# Sheet1.net
KiCad netlist of a schematic drawn in Altium Designer
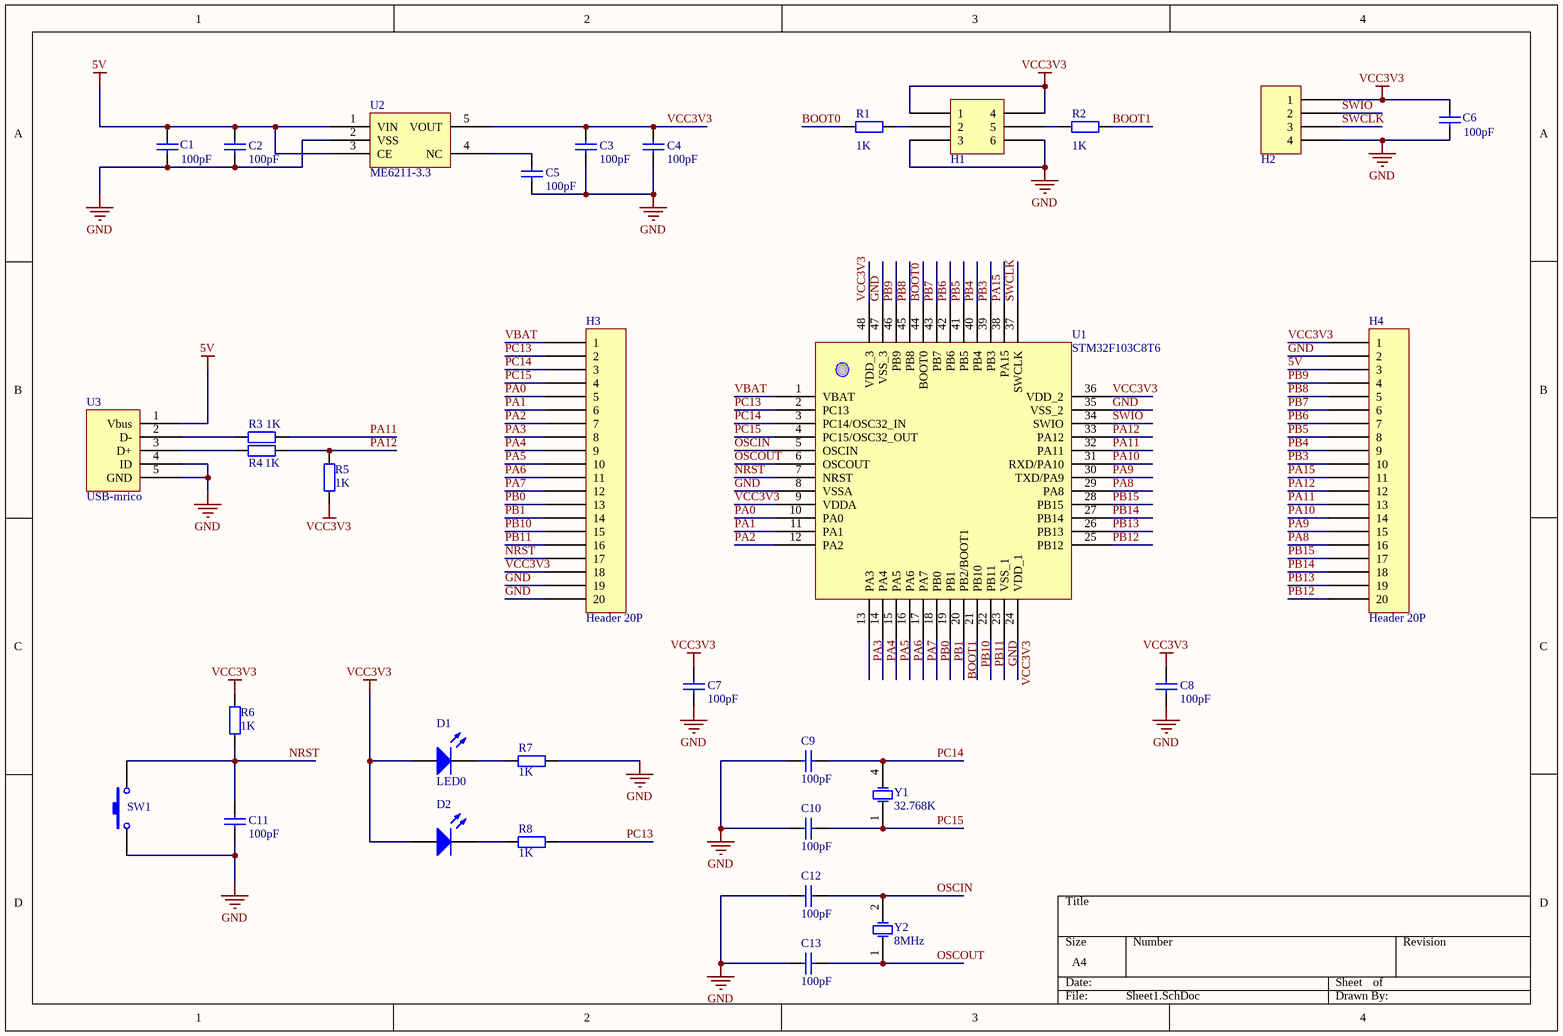
[diagram p0: Sheet1.SchDoc]

(export (version "E")
  (design (tool "Eeschema 10.0.6"))
  (components
    (comp (ref "C1")
      (value "100pF")
      (footprint "C 0603_L")
      (description "Capacitor")
      (fields (field (name "Comment") "Cap") (field (name "PUBLISHER") "Altium Limited"))
      (libsource (lib "Miscellaneous Devices") (part "Cap"))
    )
    (comp (ref "C2")
      (value "100pF")
      (footprint "C 0603_L")
      (description "Capacitor")
      (fields (field (name "Comment") "Cap") (field (name "PUBLISHER") "Altium Limited"))
      (libsource (lib "Miscellaneous Devices") (part "Cap"))
    )
    (comp (ref "C3")
      (value "100pF")
      (footprint "C 0603_L")
      (description "Capacitor")
      (fields (field (name "Comment") "Cap") (field (name "PUBLISHER") "Altium Limited"))
      (libsource (lib "Miscellaneous Devices") (part "Cap"))
    )
    (comp (ref "C4")
      (value "100pF")
      (footprint "C 0603_L")
      (description "Capacitor")
      (fields (field (name "Comment") "Cap") (field (name "PUBLISHER") "Altium Limited"))
      (libsource (lib "Miscellaneous Devices") (part "Cap"))
    )
    (comp (ref "C5")
      (value "100pF")
      (footprint "C 0805_L")
      (description "Capacitor")
      (fields (field (name "Comment") "Cap") (field (name "PUBLISHER") "Altium Limited"))
      (libsource (lib "Miscellaneous Devices") (part "Cap"))
    )
    (comp (ref "C6")
      (value "100pF")
      (footprint "C 0805_L")
      (description "Capacitor")
      (fields (field (name "Comment") "Cap") (field (name "PUBLISHER") "Altium Limited"))
      (libsource (lib "Miscellaneous Devices") (part "Cap"))
    )
    (comp (ref "C7")
      (value "100pF")
      (footprint "C 0603_L")
      (description "Capacitor")
      (fields (field (name "Comment") "Cap") (field (name "PUBLISHER") "Altium Limited"))
      (libsource (lib "Miscellaneous Devices") (part "Cap"))
    )
    (comp (ref "C8")
      (value "100pF")
      (footprint "C 0603_L")
      (description "Capacitor")
      (fields (field (name "Comment") "Cap") (field (name "PUBLISHER") "Altium Limited"))
      (libsource (lib "Miscellaneous Devices") (part "Cap"))
    )
    (comp (ref "C9")
      (value "100pF")
      (footprint "C 0603_L")
      (description "Capacitor")
      (fields (field (name "Comment") "Cap") (field (name "PUBLISHER") "Altium Limited"))
      (libsource (lib "Miscellaneous Devices") (part "Cap"))
    )
    (comp (ref "C10")
      (value "100pF")
      (footprint "C 0603_L")
      (description "Capacitor")
      (fields (field (name "Comment") "Cap") (field (name "PUBLISHER") "Altium Limited"))
      (libsource (lib "Miscellaneous Devices") (part "Cap"))
    )
    (comp (ref "C11")
      (value "100pF")
      (footprint "C 0603_L")
      (description "Capacitor")
      (fields (field (name "Comment") "Cap") (field (name "PUBLISHER") "Altium Limited"))
      (libsource (lib "Miscellaneous Devices") (part "Cap"))
    )
    (comp (ref "C12")
      (value "100pF")
      (footprint "C 0603_L")
      (description "Capacitor")
      (fields (field (name "Comment") "Cap") (field (name "PUBLISHER") "Altium Limited"))
      (libsource (lib "Miscellaneous Devices") (part "Cap"))
    )
    (comp (ref "C13")
      (value "100pF")
      (footprint "C 0603_L")
      (description "Capacitor")
      (fields (field (name "Comment") "Cap") (field (name "PUBLISHER") "Altium Limited"))
      (libsource (lib "Miscellaneous Devices") (part "Cap"))
    )
    (comp (ref "D1")
      (value "LED0")
      (footprint "LED 0603W")
      (description "Typical INFRARED GaAs LED")
      (fields (field (name "PUBLISHER") "Altium Limited"))
      (libsource (lib "Miscellaneous Devices") (part "LED0"))
    )
    (comp (ref "D2")
      (value "LED0")
      (footprint "LED 0603W")
      (description "Typical INFRARED GaAs LED")
      (fields (field (name "PUBLISHER") "Altium Limited"))
      (libsource (lib "Miscellaneous Devices") (part "LED0"))
    )
    (comp (ref "H1")
      (value "HEADER 6P")
      (footprint "HDR2.54-LI-2x3P")
      (libsource (lib "Schlib1") (part "HEADER 6P"))
    )
    (comp (ref "H2")
      (value "HEADER 4P")
      (footprint "HDR2.54-LI-4P")
      (libsource (lib "Schlib1") (part "HEADER 4P"))
    )
    (comp (ref "H3")
      (value "Header 20P")
      (footprint "HDR2.54-LI-20P")
      (libsource (lib "Schlib1") (part "HEADER 20P"))
    )
    (comp (ref "H4")
      (value "Header 20P")
      (footprint "HDR2.54-LI-20P")
      (libsource (lib "Schlib1") (part "HEADER 20P"))
    )
    (comp (ref "R1")
      (value "1K")
      (footprint "R 0603_L")
      (description "Resistor")
      (fields (field (name "Comment") "Res2") (field (name "PUBLISHER") "Altium Limited"))
      (libsource (lib "") (part "Res2_2"))
    )
    (comp (ref "R2")
      (value "1K")
      (footprint "R 0603_L")
      (description "Resistor")
      (fields (field (name "Comment") "Res2") (field (name "PUBLISHER") "Altium Limited"))
      (libsource (lib "") (part "Res2_2"))
    )
    (comp (ref "R3")
      (value "1K")
      (footprint "R 0603_L")
      (description "Resistor")
      (fields (field (name "Comment") "Res2") (field (name "PUBLISHER") "Altium Limited"))
      (libsource (lib "") (part "Res2_2"))
    )
    (comp (ref "R4")
      (value "1K")
      (footprint "R 0603_L")
      (description "Resistor")
      (fields (field (name "Comment") "Res2") (field (name "PUBLISHER") "Altium Limited"))
      (libsource (lib "") (part "Res2_2"))
    )
    (comp (ref "R5")
      (value "1K")
      (footprint "R 0603_L")
      (description "Resistor")
      (fields (field (name "Comment") "Res2") (field (name "PUBLISHER") "Altium Limited"))
      (libsource (lib "") (part "Res2_1"))
    )
    (comp (ref "R6")
      (value "1K")
      (footprint "R 0603_L")
      (description "Resistor")
      (fields (field (name "Comment") "Res2") (field (name "PUBLISHER") "Altium Limited"))
      (libsource (lib "") (part "Res2_1"))
    )
    (comp (ref "R7")
      (value "1K")
      (footprint "R 0603_L")
      (description "Resistor")
      (fields (field (name "Comment") "Res2") (field (name "PUBLISHER") "Altium Limited"))
      (libsource (lib "Miscellaneous Devices") (part "Res2"))
    )
    (comp (ref "R8")
      (value "1K")
      (footprint "R 0603_L")
      (description "Resistor")
      (fields (field (name "Comment") "Res2") (field (name "PUBLISHER") "Altium Limited"))
      (libsource (lib "Miscellaneous Devices") (part "Res2"))
    )
    (comp (ref "SW1")
      (value "SW-PB")
      (footprint "TSW SMD-3*6*4.3")
      (description "Switch")
      (fields (field (name "PUBLISHER") "Altium Limited"))
      (libsource (lib "Miscellaneous Devices") (part "SW-PB"))
    )
    (comp (ref "U1")
      (value "STM32F103C8T6")
      (footprint "LQFP48_N")
      (libsource (lib "Schlib1") (part "STM32F103C8T6"))
    )
    (comp (ref "U2")
      (value "ME6211-3.3")
      (footprint "SOT23-5")
      (libsource (lib "Schlib1") (part "ME6211-3.3"))
    )
    (comp (ref "U3")
      (value "USB-mrico")
      (footprint "USB-MICRO_B")
      (libsource (lib "Schlib1") (part "USB-mrico"))
    )
    (comp (ref "Y1")
      (value "32.768K")
      (footprint "OSC MC-306")
      (description "Crystal Oscillator")
      (fields (field (name "PUBLISHER") "Altium Limited"))
      (libsource (lib "Miscellaneous Devices") (part "XTAL"))
    )
    (comp (ref "Y2")
      (value "8MHz")
      (footprint "OSC HC-49S")
      (description "Crystal Oscillator")
      (fields (field (name "PUBLISHER") "Altium Limited"))
      (libsource (lib "") (part "XTAL_1"))
    )
  )
  (nets
    (net (code "1") (name "/BOOT0") (class "Default")
      (node (ref "R1") (pin "1") (pinfunction "1_1") (pintype "passive"))
      (node (ref "U1") (pin "44") (pinfunction "BOOT0_44") (pintype "passive"))
    )
    (net (code "2") (name "/BOOT1") (class "Default")
      (node (ref "R2") (pin "2") (pinfunction "2_2") (pintype "passive"))
      (node (ref "U1") (pin "20") (pinfunction "PB2/BOOT1_20") (pintype "passive"))
    )
    (net (code "3") (name "/NRST") (class "Default")
      (node (ref "C11") (pin "2") (pinfunction "2_2") (pintype "passive"))
      (node (ref "H3") (pin "17") (pinfunction "17_17") (pintype "passive"))
      (node (ref "R6") (pin "1") (pinfunction "1_1") (pintype "passive"))
      (node (ref "SW1") (pin "2") (pinfunction "2_2") (pintype "passive"))
      (node (ref "U1") (pin "7") (pinfunction "NRST_7") (pintype "passive"))
    )
    (net (code "4") (name "/OSCIN") (class "Default")
      (node (ref "C12") (pin "1") (pinfunction "1_1") (pintype "passive"))
      (node (ref "U1") (pin "5") (pinfunction "OSCIN_5") (pintype "passive"))
      (node (ref "Y2") (pin "2") (pinfunction "OSC2_2") (pintype "passive"))
    )
    (net (code "5") (name "/OSCOUT") (class "Default")
      (node (ref "C13") (pin "1") (pinfunction "1_1") (pintype "passive"))
      (node (ref "U1") (pin "6") (pinfunction "OSCOUT_6") (pintype "passive"))
      (node (ref "Y2") (pin "1") (pinfunction "OSC1_1") (pintype "passive"))
    )
    (net (code "6") (name "/PA0") (class "Default")
      (node (ref "H3") (pin "5") (pinfunction "5_5") (pintype "passive"))
      (node (ref "U1") (pin "10") (pinfunction "PA0_10") (pintype "passive"))
    )
    (net (code "7") (name "/PA1") (class "Default")
      (node (ref "H3") (pin "6") (pinfunction "6_6") (pintype "passive"))
      (node (ref "U1") (pin "11") (pinfunction "PA1_11") (pintype "passive"))
    )
    (net (code "8") (name "/PA2") (class "Default")
      (node (ref "H3") (pin "7") (pinfunction "7_7") (pintype "passive"))
      (node (ref "U1") (pin "12") (pinfunction "PA2_12") (pintype "passive"))
    )
    (net (code "9") (name "/PA3") (class "Default")
      (node (ref "H3") (pin "8") (pinfunction "8_8") (pintype "passive"))
      (node (ref "U1") (pin "13") (pinfunction "PA3_13") (pintype "passive"))
    )
    (net (code "10") (name "/PA4") (class "Default")
      (node (ref "H3") (pin "9") (pinfunction "9_9") (pintype "passive"))
      (node (ref "U1") (pin "14") (pinfunction "PA4_14") (pintype "passive"))
    )
    (net (code "11") (name "/PA5") (class "Default")
      (node (ref "H3") (pin "10") (pinfunction "10_10") (pintype "passive"))
      (node (ref "U1") (pin "15") (pinfunction "PA5_15") (pintype "passive"))
    )
    (net (code "12") (name "/PA6") (class "Default")
      (node (ref "H3") (pin "11") (pinfunction "11_11") (pintype "passive"))
      (node (ref "U1") (pin "16") (pinfunction "PA6_16") (pintype "passive"))
    )
    (net (code "13") (name "/PA7") (class "Default")
      (node (ref "H3") (pin "12") (pinfunction "12_12") (pintype "passive"))
      (node (ref "U1") (pin "17") (pinfunction "PA7_17") (pintype "passive"))
    )
    (net (code "14") (name "/PA8") (class "Default")
      (node (ref "H4") (pin "16") (pinfunction "16_16") (pintype "passive"))
      (node (ref "U1") (pin "29") (pinfunction "PA8_29") (pintype "passive"))
    )
    (net (code "15") (name "/PA9") (class "Default")
      (node (ref "H4") (pin "15") (pinfunction "15_15") (pintype "passive"))
      (node (ref "U1") (pin "30") (pinfunction "TXD/PA9_30") (pintype "passive"))
    )
    (net (code "16") (name "/PA10") (class "Default")
      (node (ref "H4") (pin "14") (pinfunction "14_14") (pintype "passive"))
      (node (ref "U1") (pin "31") (pinfunction "RXD/PA10_31") (pintype "passive"))
    )
    (net (code "17") (name "/PA11") (class "Default")
      (node (ref "H4") (pin "13") (pinfunction "13_13") (pintype "passive"))
      (node (ref "R3") (pin "2") (pinfunction "2_2") (pintype "passive"))
      (node (ref "U1") (pin "32") (pinfunction "PA11_32") (pintype "passive"))
    )
    (net (code "18") (name "/PA12") (class "Default")
      (node (ref "H4") (pin "12") (pinfunction "12_12") (pintype "passive"))
      (node (ref "R4") (pin "2") (pinfunction "2_2") (pintype "passive"))
      (node (ref "R5") (pin "2") (pinfunction "2_2") (pintype "passive"))
      (node (ref "U1") (pin "33") (pinfunction "PA12_33") (pintype "passive"))
    )
    (net (code "19") (name "/PA15") (class "Default")
      (node (ref "H4") (pin "11") (pinfunction "11_11") (pintype "passive"))
      (node (ref "U1") (pin "38") (pinfunction "PA15_38") (pintype "passive"))
    )
    (net (code "20") (name "/PB0") (class "Default")
      (node (ref "H3") (pin "13") (pinfunction "13_13") (pintype "passive"))
      (node (ref "U1") (pin "18") (pinfunction "PB0_18") (pintype "passive"))
    )
    (net (code "21") (name "/PB1") (class "Default")
      (node (ref "H3") (pin "14") (pinfunction "14_14") (pintype "passive"))
      (node (ref "U1") (pin "19") (pinfunction "PB1_19") (pintype "passive"))
    )
    (net (code "22") (name "/PB3") (class "Default")
      (node (ref "H4") (pin "10") (pinfunction "10_10") (pintype "passive"))
      (node (ref "U1") (pin "39") (pinfunction "PB3_39") (pintype "passive"))
    )
    (net (code "23") (name "/PB4") (class "Default")
      (node (ref "H4") (pin "9") (pinfunction "9_9") (pintype "passive"))
      (node (ref "U1") (pin "40") (pinfunction "PB4_40") (pintype "passive"))
    )
    (net (code "24") (name "/PB5") (class "Default")
      (node (ref "H4") (pin "8") (pinfunction "8_8") (pintype "passive"))
      (node (ref "U1") (pin "41") (pinfunction "PB5_41") (pintype "passive"))
    )
    (net (code "25") (name "/PB6") (class "Default")
      (node (ref "H4") (pin "7") (pinfunction "7_7") (pintype "passive"))
      (node (ref "U1") (pin "42") (pinfunction "PB6_42") (pintype "passive"))
    )
    (net (code "26") (name "/PB7") (class "Default")
      (node (ref "H4") (pin "6") (pinfunction "6_6") (pintype "passive"))
      (node (ref "U1") (pin "43") (pinfunction "PB7_43") (pintype "passive"))
    )
    (net (code "27") (name "/PB8") (class "Default")
      (node (ref "H4") (pin "5") (pinfunction "5_5") (pintype "passive"))
      (node (ref "U1") (pin "45") (pinfunction "PB8_45") (pintype "passive"))
    )
    (net (code "28") (name "/PB9") (class "Default")
      (node (ref "H4") (pin "4") (pinfunction "4_4") (pintype "passive"))
      (node (ref "U1") (pin "46") (pinfunction "PB9_46") (pintype "passive"))
    )
    (net (code "29") (name "/PB10") (class "Default")
      (node (ref "H3") (pin "15") (pinfunction "15_15") (pintype "passive"))
      (node (ref "U1") (pin "21") (pinfunction "PB10_21") (pintype "passive"))
    )
    (net (code "30") (name "/PB11") (class "Default")
      (node (ref "H3") (pin "16") (pinfunction "16_16") (pintype "passive"))
      (node (ref "U1") (pin "22") (pinfunction "PB11_22") (pintype "passive"))
    )
    (net (code "31") (name "/PB12") (class "Default")
      (node (ref "H4") (pin "20") (pinfunction "20_20") (pintype "passive"))
      (node (ref "U1") (pin "25") (pinfunction "PB12_25") (pintype "passive"))
    )
    (net (code "32") (name "/PB13") (class "Default")
      (node (ref "H4") (pin "19") (pinfunction "19_19") (pintype "passive"))
      (node (ref "U1") (pin "26") (pinfunction "PB13_26") (pintype "passive"))
    )
    (net (code "33") (name "/PB14") (class "Default")
      (node (ref "H4") (pin "18") (pinfunction "18_18") (pintype "passive"))
      (node (ref "U1") (pin "27") (pinfunction "PB14_27") (pintype "passive"))
    )
    (net (code "34") (name "/PB15") (class "Default")
      (node (ref "H4") (pin "17") (pinfunction "17_17") (pintype "passive"))
      (node (ref "U1") (pin "28") (pinfunction "PB15_28") (pintype "passive"))
    )
    (net (code "35") (name "/PC13") (class "Default")
      (node (ref "H3") (pin "2") (pinfunction "2_2") (pintype "passive"))
      (node (ref "R8") (pin "1") (pinfunction "1_1") (pintype "passive"))
      (node (ref "U1") (pin "2") (pinfunction "PC13_2") (pintype "passive"))
    )
    (net (code "36") (name "/PC14") (class "Default")
      (node (ref "C9") (pin "1") (pinfunction "1_1") (pintype "passive"))
      (node (ref "H3") (pin "3") (pinfunction "3_3") (pintype "passive"))
      (node (ref "U1") (pin "3") (pinfunction "PC14/OSC32_IN_3") (pintype "passive"))
      (node (ref "Y1") (pin "4") (pinfunction "OSC4_4") (pintype "passive"))
    )
    (net (code "37") (name "/PC15") (class "Default")
      (node (ref "C10") (pin "1") (pinfunction "1_1") (pintype "passive"))
      (node (ref "H3") (pin "4") (pinfunction "4_4") (pintype "passive"))
      (node (ref "U1") (pin "4") (pinfunction "PC15/OSC32_OUT_4") (pintype "passive"))
      (node (ref "Y1") (pin "1") (pinfunction "OSC1_1") (pintype "passive"))
    )
    (net (code "38") (name "/SWCLK") (class "Default")
      (node (ref "H2") (pin "3") (pinfunction "3_3") (pintype "passive"))
      (node (ref "U1") (pin "37") (pinfunction "SWCLK_37") (pintype "passive"))
    )
    (net (code "39") (name "/SWIO") (class "Default")
      (node (ref "H2") (pin "2") (pinfunction "2_2") (pintype "passive"))
      (node (ref "U1") (pin "34") (pinfunction "SWIO_34") (pintype "passive"))
    )
    (net (code "40") (name "/VBAT") (class "Default")
      (node (ref "H3") (pin "1") (pinfunction "1_1") (pintype "passive"))
      (node (ref "U1") (pin "1") (pinfunction "VBAT_1") (pintype "passive"))
    )
    (net (code "41") (name "5V") (class "Default")
      (node (ref "C1") (pin "2") (pinfunction "2_2") (pintype "passive"))
      (node (ref "C2") (pin "2") (pinfunction "2_2") (pintype "passive"))
      (node (ref "H4") (pin "3") (pinfunction "3_3") (pintype "passive"))
      (node (ref "U2") (pin "1") (pinfunction "VIN_1") (pintype "passive"))
      (node (ref "U2") (pin "3") (pinfunction "CE_3") (pintype "passive"))
      (node (ref "U3") (pin "1") (pinfunction "Vbus_1") (pintype "passive"))
    )
    (net (code "42") (name "GND") (class "Default")
      (node (ref "C1") (pin "1") (pinfunction "1_1") (pintype "passive"))
      (node (ref "C10") (pin "2") (pinfunction "2_2") (pintype "passive"))
      (node (ref "C11") (pin "1") (pinfunction "1_1") (pintype "passive"))
      (node (ref "C12") (pin "2") (pinfunction "2_2") (pintype "passive"))
      (node (ref "C13") (pin "2") (pinfunction "2_2") (pintype "passive"))
      (node (ref "C2") (pin "1") (pinfunction "1_1") (pintype "passive"))
      (node (ref "C3") (pin "1") (pinfunction "1_1") (pintype "passive"))
      (node (ref "C4") (pin "1") (pinfunction "1_1") (pintype "passive"))
      (node (ref "C5") (pin "1") (pinfunction "1_1") (pintype "passive"))
      (node (ref "C6") (pin "1") (pinfunction "1_1") (pintype "passive"))
      (node (ref "C7") (pin "1") (pinfunction "1_1") (pintype "passive"))
      (node (ref "C8") (pin "1") (pinfunction "1_1") (pintype "passive"))
      (node (ref "C9") (pin "2") (pinfunction "2_2") (pintype "passive"))
      (node (ref "H1") (pin "3") (pinfunction "3_3") (pintype "passive"))
      (node (ref "H1") (pin "6") (pinfunction "6_6") (pintype "passive"))
      (node (ref "H2") (pin "4") (pinfunction "4_4") (pintype "passive"))
      (node (ref "H3") (pin "19") (pinfunction "19_19") (pintype "passive"))
      (node (ref "H3") (pin "20") (pinfunction "20_20") (pintype "passive"))
      (node (ref "H4") (pin "2") (pinfunction "2_2") (pintype "passive"))
      (node (ref "R7") (pin "1") (pinfunction "1_1") (pintype "passive"))
      (node (ref "SW1") (pin "1") (pinfunction "1_1") (pintype "passive"))
      (node (ref "U1") (pin "23") (pinfunction "VSS_1_23") (pintype "passive"))
      (node (ref "U1") (pin "35") (pinfunction "VSS_2_35") (pintype "passive"))
      (node (ref "U1") (pin "47") (pinfunction "VSS_3_47") (pintype "passive"))
      (node (ref "U1") (pin "8") (pinfunction "VSSA_8") (pintype "passive"))
      (node (ref "U2") (pin "2") (pinfunction "VSS_2") (pintype "passive"))
      (node (ref "U3") (pin "4") (pinfunction "ID_4") (pintype "passive"))
      (node (ref "U3") (pin "5") (pinfunction "GND_5") (pintype "passive"))
    )
    (net (code "43") (name "Net-(D1-K)") (class "Default")
      (node (ref "D1") (pin "2") (pinfunction "K_2") (pintype "passive"))
      (node (ref "R7") (pin "2") (pinfunction "2_2") (pintype "passive"))
    )
    (net (code "44") (name "Net-(D2-K)") (class "Default")
      (node (ref "D2") (pin "2") (pinfunction "K_2") (pintype "passive"))
      (node (ref "R8") (pin "2") (pinfunction "2_2") (pintype "passive"))
    )
    (net (code "45") (name "Net-(H1-Pad2)") (class "Default")
      (node (ref "H1") (pin "2") (pinfunction "2_2") (pintype "passive"))
      (node (ref "R1") (pin "2") (pinfunction "2_2") (pintype "passive"))
    )
    (net (code "46") (name "Net-(H1-Pad5)") (class "Default")
      (node (ref "H1") (pin "5") (pinfunction "5_5") (pintype "passive"))
      (node (ref "R2") (pin "1") (pinfunction "1_1") (pintype "passive"))
    )
    (net (code "47") (name "Net-(U2-NC)") (class "Default")
      (node (ref "C5") (pin "2") (pinfunction "2_2") (pintype "passive"))
      (node (ref "U2") (pin "4") (pinfunction "NC_4") (pintype "passive"))
    )
    (net (code "48") (name "Net-(U3-D+)") (class "Default")
      (node (ref "R4") (pin "1") (pinfunction "1_1") (pintype "passive"))
      (node (ref "U3") (pin "3") (pinfunction "D+_3") (pintype "passive"))
    )
    (net (code "49") (name "Net-(U3-D-)") (class "Default")
      (node (ref "R3") (pin "1") (pinfunction "1_1") (pintype "passive"))
      (node (ref "U3") (pin "2") (pinfunction "D-_2") (pintype "passive"))
    )
    (net (code "50") (name "VCC3V3") (class "Default")
      (node (ref "C3") (pin "2") (pinfunction "2_2") (pintype "passive"))
      (node (ref "C4") (pin "2") (pinfunction "2_2") (pintype "passive"))
      (node (ref "C6") (pin "2") (pinfunction "2_2") (pintype "passive"))
      (node (ref "C7") (pin "2") (pinfunction "2_2") (pintype "passive"))
      (node (ref "C8") (pin "2") (pinfunction "2_2") (pintype "passive"))
      (node (ref "D1") (pin "1") (pinfunction "A_1") (pintype "passive"))
      (node (ref "D2") (pin "1") (pinfunction "A_1") (pintype "passive"))
      (node (ref "H1") (pin "1") (pinfunction "1_1") (pintype "passive"))
      (node (ref "H1") (pin "4") (pinfunction "4_4") (pintype "passive"))
      (node (ref "H2") (pin "1") (pinfunction "1_1") (pintype "passive"))
      (node (ref "H3") (pin "18") (pinfunction "18_18") (pintype "passive"))
      (node (ref "H4") (pin "1") (pinfunction "1_1") (pintype "passive"))
      (node (ref "R5") (pin "1") (pinfunction "1_1") (pintype "passive"))
      (node (ref "R6") (pin "2") (pinfunction "2_2") (pintype "passive"))
      (node (ref "U1") (pin "24") (pinfunction "VDD_1_24") (pintype "passive"))
      (node (ref "U1") (pin "36") (pinfunction "VDD_2_36") (pintype "passive"))
      (node (ref "U1") (pin "48") (pinfunction "VDD_3_48") (pintype "passive"))
      (node (ref "U1") (pin "9") (pinfunction "VDDA_9") (pintype "passive"))
      (node (ref "U2") (pin "5") (pinfunction "VOUT_5") (pintype "passive"))
    )
  )
)
